# LCD_News_Ticker.net
KiCad netlist of a schematic drawn in EasyEDA
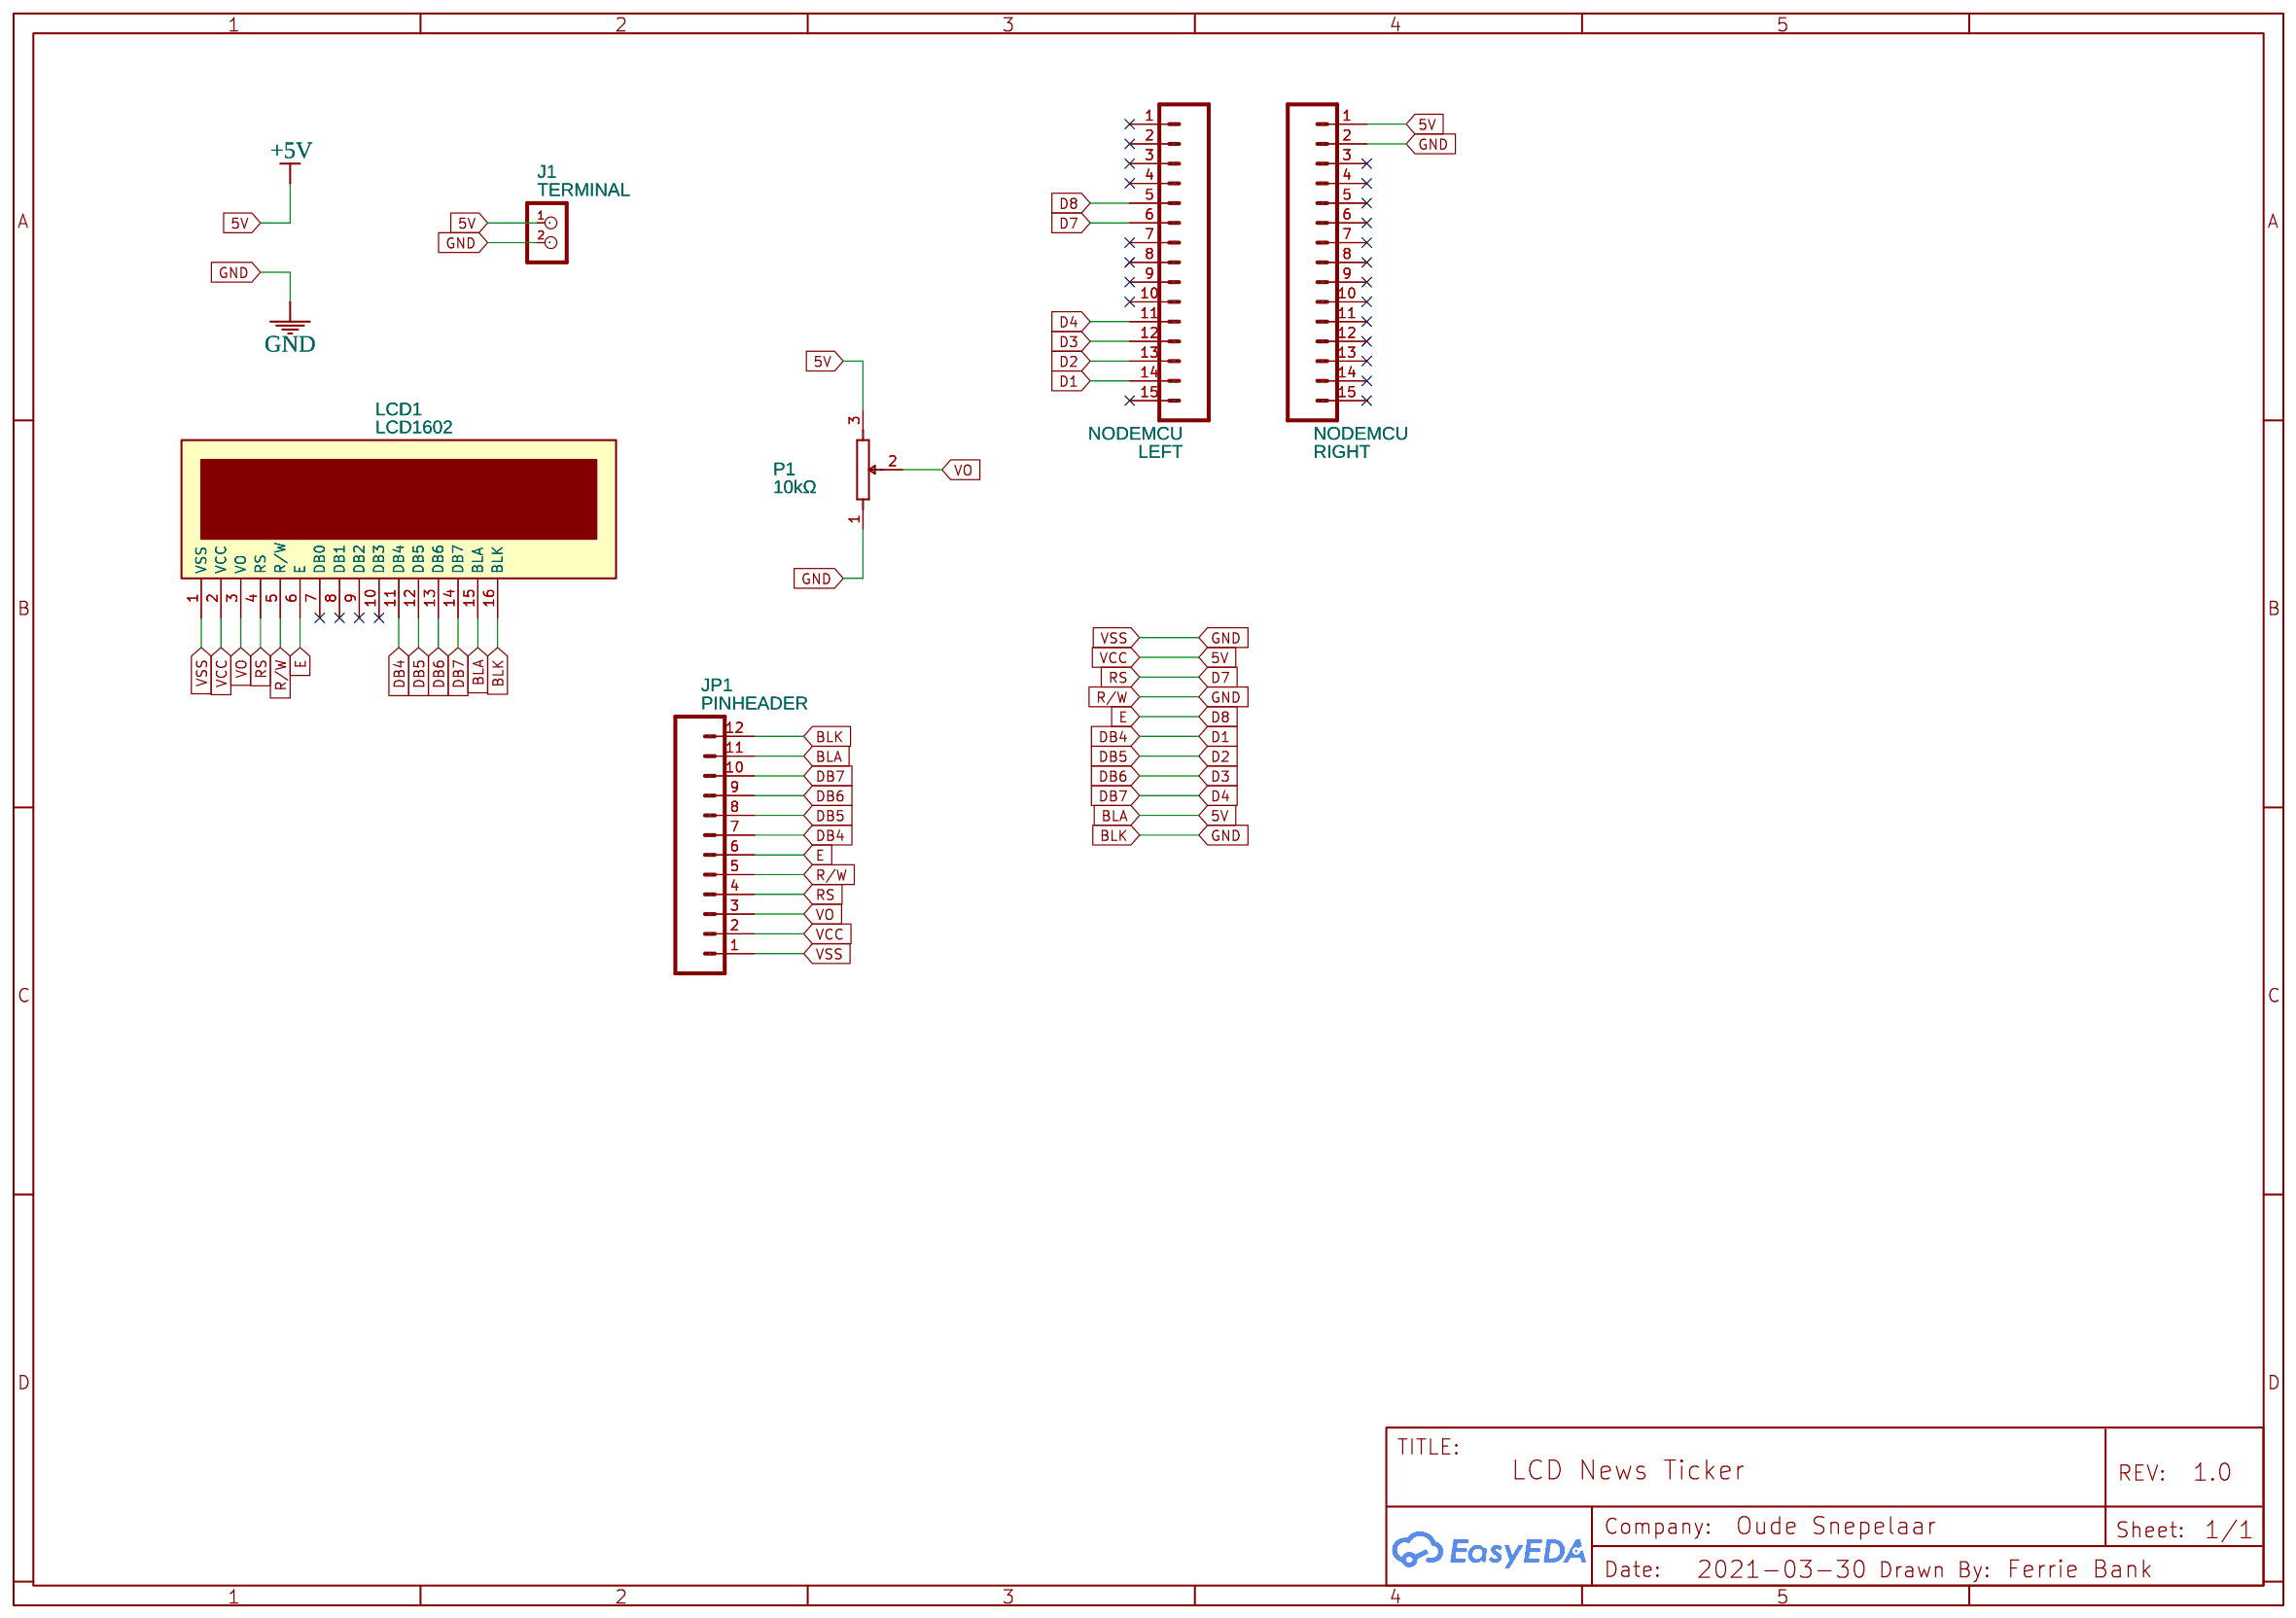
[diagram p0: schematic sheet]

(export (version "E")
  (design (tool "Eeschema 10.0.6"))
  (components
    (comp (ref "J1") (value "TERMINAL") (libsource (lib "") (part "CON_TERMINAL_BLOCK_02-5MM")))
    (comp (ref "JP1") (value "PINHEADER") (libsource (lib "") (part "M12PTH")))
    (comp (ref "LCD1")
      (value "LCD1602")
      (fields
        (field (name "BOM_Manufacturer Part") "LCM1602K-NSW-BBW")
        (field (name "BOM_Supplier Part") "C83275")
      )
      (libsource (lib "") (part "LCD1602"))
    )
    (comp (ref "LEFT") (value "NODEMCU") (libsource (lib "") (part "M15")))
    (comp (ref "P1") (value "10kΩ") (libsource (lib "") (part "POTF_1")))
    (comp (ref "RIGHT") (value "NODEMCU") (libsource (lib "") (part "M15_1")))
  )
  (nets
    (net (code "1") (name "5V") (class "Default")
      (node (ref "J1") (pin "1") (pinfunction "1_1") (pintype "unspecified"))
      (node (ref "JP1") (pin "11") (pinfunction "11_11") (pintype "unspecified"))
      (node (ref "JP1") (pin "2") (pinfunction "2_2") (pintype "unspecified"))
      (node (ref "LCD1") (pin "15") (pinfunction "BLA_15") (pintype "unspecified"))
      (node (ref "LCD1") (pin "2") (pinfunction "VCC_2") (pintype "unspecified"))
      (node (ref "P1") (pin "3") (pinfunction "3_3") (pintype "unspecified"))
      (node (ref "RIGHT") (pin "1") (pinfunction "1_1") (pintype "unspecified"))
    )
    (net (code "2") (name "BLK") (class "Default")
      (node (ref "J1") (pin "2") (pinfunction "2_2") (pintype "unspecified"))
      (node (ref "JP1") (pin "1") (pinfunction "1_1") (pintype "unspecified"))
      (node (ref "JP1") (pin "12") (pinfunction "12_12") (pintype "unspecified"))
      (node (ref "JP1") (pin "5") (pinfunction "5_5") (pintype "unspecified"))
      (node (ref "LCD1") (pin "1") (pinfunction "VSS_1") (pintype "unspecified"))
      (node (ref "LCD1") (pin "16") (pinfunction "BLK_16") (pintype "unspecified"))
      (node (ref "LCD1") (pin "5") (pinfunction "R/W_5") (pintype "unspecified"))
      (node (ref "P1") (pin "1") (pinfunction "1_1") (pintype "unspecified"))
      (node (ref "RIGHT") (pin "2") (pinfunction "2_2") (pintype "unspecified"))
    )
    (net (code "3") (name "D1") (class "Default")
      (node (ref "JP1") (pin "7") (pinfunction "7_7") (pintype "unspecified"))
      (node (ref "LCD1") (pin "11") (pinfunction "DB4_11") (pintype "unspecified"))
      (node (ref "LEFT") (pin "14") (pinfunction "14_14") (pintype "unspecified"))
    )
    (net (code "4") (name "D2") (class "Default")
      (node (ref "JP1") (pin "8") (pinfunction "8_8") (pintype "unspecified"))
      (node (ref "LCD1") (pin "12") (pinfunction "DB5_12") (pintype "unspecified"))
      (node (ref "LEFT") (pin "13") (pinfunction "13_13") (pintype "unspecified"))
    )
    (net (code "5") (name "D3") (class "Default")
      (node (ref "JP1") (pin "9") (pinfunction "9_9") (pintype "unspecified"))
      (node (ref "LCD1") (pin "13") (pinfunction "DB6_13") (pintype "unspecified"))
      (node (ref "LEFT") (pin "12") (pinfunction "12_12") (pintype "unspecified"))
    )
    (net (code "6") (name "D4") (class "Default")
      (node (ref "JP1") (pin "10") (pinfunction "10_10") (pintype "unspecified"))
      (node (ref "LCD1") (pin "14") (pinfunction "DB7_14") (pintype "unspecified"))
      (node (ref "LEFT") (pin "11") (pinfunction "11_11") (pintype "unspecified"))
    )
    (net (code "7") (name "D7") (class "Default")
      (node (ref "JP1") (pin "4") (pinfunction "4_4") (pintype "unspecified"))
      (node (ref "LCD1") (pin "4") (pinfunction "RS_4") (pintype "unspecified"))
      (node (ref "LEFT") (pin "6") (pinfunction "6_6") (pintype "unspecified"))
    )
    (net (code "8") (name "D8") (class "Default")
      (node (ref "JP1") (pin "6") (pinfunction "6_6") (pintype "unspecified"))
      (node (ref "LCD1") (pin "6") (pinfunction "E_6") (pintype "unspecified"))
      (node (ref "LEFT") (pin "5") (pinfunction "5_5") (pintype "unspecified"))
    )
    (net (code "9") (name "VO") (class "Default")
      (node (ref "JP1") (pin "3") (pinfunction "3_3") (pintype "unspecified"))
      (node (ref "LCD1") (pin "3") (pinfunction "VO_3") (pintype "unspecified"))
      (node (ref "P1") (pin "2") (pinfunction "2_2") (pintype "unspecified"))
    )
    (net (code "10") (name "unconnected-(LCD1-DB0-Pad7)") (class "Default")
      (node (ref "LCD1") (pin "7") (pinfunction "DB0_7") (pintype "unspecified+no_connect"))
    )
    (net (code "11") (name "unconnected-(LCD1-DB1-Pad8)") (class "Default")
      (node (ref "LCD1") (pin "8") (pinfunction "DB1_8") (pintype "unspecified+no_connect"))
    )
    (net (code "12") (name "unconnected-(LCD1-DB2-Pad9)") (class "Default")
      (node (ref "LCD1") (pin "9") (pinfunction "DB2_9") (pintype "unspecified+no_connect"))
    )
    (net (code "13") (name "unconnected-(LCD1-DB3-Pad10)") (class "Default")
      (node (ref "LCD1") (pin "10") (pinfunction "DB3_10") (pintype "unspecified+no_connect"))
    )
    (net (code "14") (name "unconnected-(LEFT-Pad1)") (class "Default")
      (node (ref "LEFT") (pin "1") (pinfunction "1_1") (pintype "unspecified+no_connect"))
    )
    (net (code "15") (name "unconnected-(LEFT-Pad2)") (class "Default")
      (node (ref "LEFT") (pin "2") (pinfunction "2_2") (pintype "unspecified+no_connect"))
    )
    (net (code "16") (name "unconnected-(LEFT-Pad3)") (class "Default")
      (node (ref "LEFT") (pin "3") (pinfunction "3_3") (pintype "unspecified+no_connect"))
    )
    (net (code "17") (name "unconnected-(LEFT-Pad4)") (class "Default")
      (node (ref "LEFT") (pin "4") (pinfunction "4_4") (pintype "unspecified+no_connect"))
    )
    (net (code "18") (name "unconnected-(LEFT-Pad7)") (class "Default")
      (node (ref "LEFT") (pin "7") (pinfunction "7_7") (pintype "unspecified+no_connect"))
    )
    (net (code "19") (name "unconnected-(LEFT-Pad8)") (class "Default")
      (node (ref "LEFT") (pin "8") (pinfunction "8_8") (pintype "unspecified+no_connect"))
    )
    (net (code "20") (name "unconnected-(LEFT-Pad9)") (class "Default")
      (node (ref "LEFT") (pin "9") (pinfunction "9_9") (pintype "unspecified+no_connect"))
    )
    (net (code "21") (name "unconnected-(LEFT-Pad10)") (class "Default")
      (node (ref "LEFT") (pin "10") (pinfunction "10_10") (pintype "unspecified+no_connect"))
    )
    (net (code "22") (name "unconnected-(LEFT-Pad15)") (class "Default")
      (node (ref "LEFT") (pin "15") (pinfunction "15_15") (pintype "unspecified+no_connect"))
    )
    (net (code "23") (name "unconnected-(RIGHT-Pad3)") (class "Default")
      (node (ref "RIGHT") (pin "3") (pinfunction "3_3") (pintype "unspecified+no_connect"))
    )
    (net (code "24") (name "unconnected-(RIGHT-Pad4)") (class "Default")
      (node (ref "RIGHT") (pin "4") (pinfunction "4_4") (pintype "unspecified+no_connect"))
    )
    (net (code "25") (name "unconnected-(RIGHT-Pad5)") (class "Default")
      (node (ref "RIGHT") (pin "5") (pinfunction "5_5") (pintype "unspecified+no_connect"))
    )
    (net (code "26") (name "unconnected-(RIGHT-Pad6)") (class "Default")
      (node (ref "RIGHT") (pin "6") (pinfunction "6_6") (pintype "unspecified+no_connect"))
    )
    (net (code "27") (name "unconnected-(RIGHT-Pad7)") (class "Default")
      (node (ref "RIGHT") (pin "7") (pinfunction "7_7") (pintype "unspecified+no_connect"))
    )
    (net (code "28") (name "unconnected-(RIGHT-Pad8)") (class "Default")
      (node (ref "RIGHT") (pin "8") (pinfunction "8_8") (pintype "unspecified+no_connect"))
    )
    (net (code "29") (name "unconnected-(RIGHT-Pad9)") (class "Default")
      (node (ref "RIGHT") (pin "9") (pinfunction "9_9") (pintype "unspecified+no_connect"))
    )
    (net (code "30") (name "unconnected-(RIGHT-Pad10)") (class "Default")
      (node (ref "RIGHT") (pin "10") (pinfunction "10_10") (pintype "unspecified+no_connect"))
    )
    (net (code "31") (name "unconnected-(RIGHT-Pad11)") (class "Default")
      (node (ref "RIGHT") (pin "11") (pinfunction "11_11") (pintype "unspecified+no_connect"))
    )
    (net (code "32") (name "unconnected-(RIGHT-Pad12)") (class "Default")
      (node (ref "RIGHT") (pin "12") (pinfunction "12_12") (pintype "unspecified+no_connect"))
    )
    (net (code "33") (name "unconnected-(RIGHT-Pad13)") (class "Default")
      (node (ref "RIGHT") (pin "13") (pinfunction "13_13") (pintype "unspecified+no_connect"))
    )
    (net (code "34") (name "unconnected-(RIGHT-Pad14)") (class "Default")
      (node (ref "RIGHT") (pin "14") (pinfunction "14_14") (pintype "unspecified+no_connect"))
    )
    (net (code "35") (name "unconnected-(RIGHT-Pad15)") (class "Default")
      (node (ref "RIGHT") (pin "15") (pinfunction "15_15") (pintype "unspecified+no_connect"))
    )
  )
)
